# Schematic.net
KiCad netlist of a schematic drawn in Altium Designer
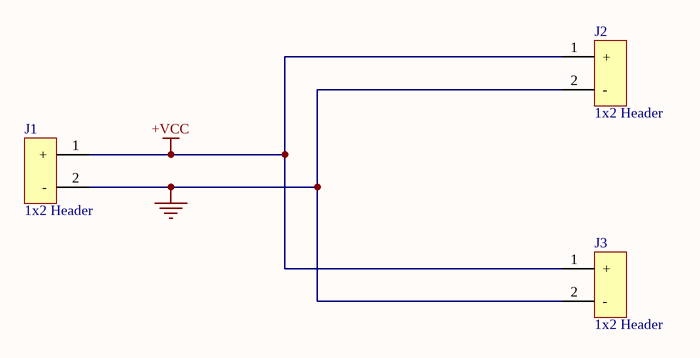
[diagram p0: Schematic.SchDoc]

(export (version "E")
  (design (tool "Eeschema 10.0.6"))
  (components
    (comp (ref "J1")
      (value "1x2 Header")
      (footprint "HDR1X2")
      (description "Headers & Wire Housings 2 PIN F/LK HEADER")
      (fields (field (name "MANUFACTURER") "Molex") (field (name "MANUFACTURER PART NUMBER") "22-29-2021"))
      (libsource (lib "") (part "22-29-2021_1"))
    )
    (comp (ref "J2")
      (value "1x2 Header")
      (footprint "HDR1X2")
      (description "Headers & Wire Housings 2 PIN F/LK HEADER")
      (fields (field (name "MANUFACTURER") "Molex") (field (name "MANUFACTURER PART NUMBER") "22-29-2021"))
      (libsource (lib "Schlib") (part "22-29-2021"))
    )
    (comp (ref "J3")
      (value "1x2 Header")
      (footprint "HDR1X2")
      (description "Headers & Wire Housings 2 PIN F/LK HEADER")
      (fields (field (name "MANUFACTURER") "Molex") (field (name "MANUFACTURER PART NUMBER") "22-29-2021"))
      (libsource (lib "Schlib") (part "22-29-2021"))
    )
  )
  (nets
    (net (code "1") (name "+VCC") (class "Default")
      (node (ref "J1") (pin "1") (pinfunction "+_1") (pintype "passive"))
      (node (ref "J2") (pin "1") (pinfunction "+_1") (pintype "passive"))
      (node (ref "J3") (pin "1") (pinfunction "+_1") (pintype "passive"))
    )
    (net (code "2") (name "GND") (class "Default")
      (node (ref "J1") (pin "2") (pinfunction "-_2") (pintype "passive"))
      (node (ref "J2") (pin "2") (pinfunction "-_2") (pintype "passive"))
      (node (ref "J3") (pin "2") (pinfunction "-_2") (pintype "passive"))
    )
  )
)
